# Sheet1.net
KiCad netlist of a schematic drawn in Altium Designer
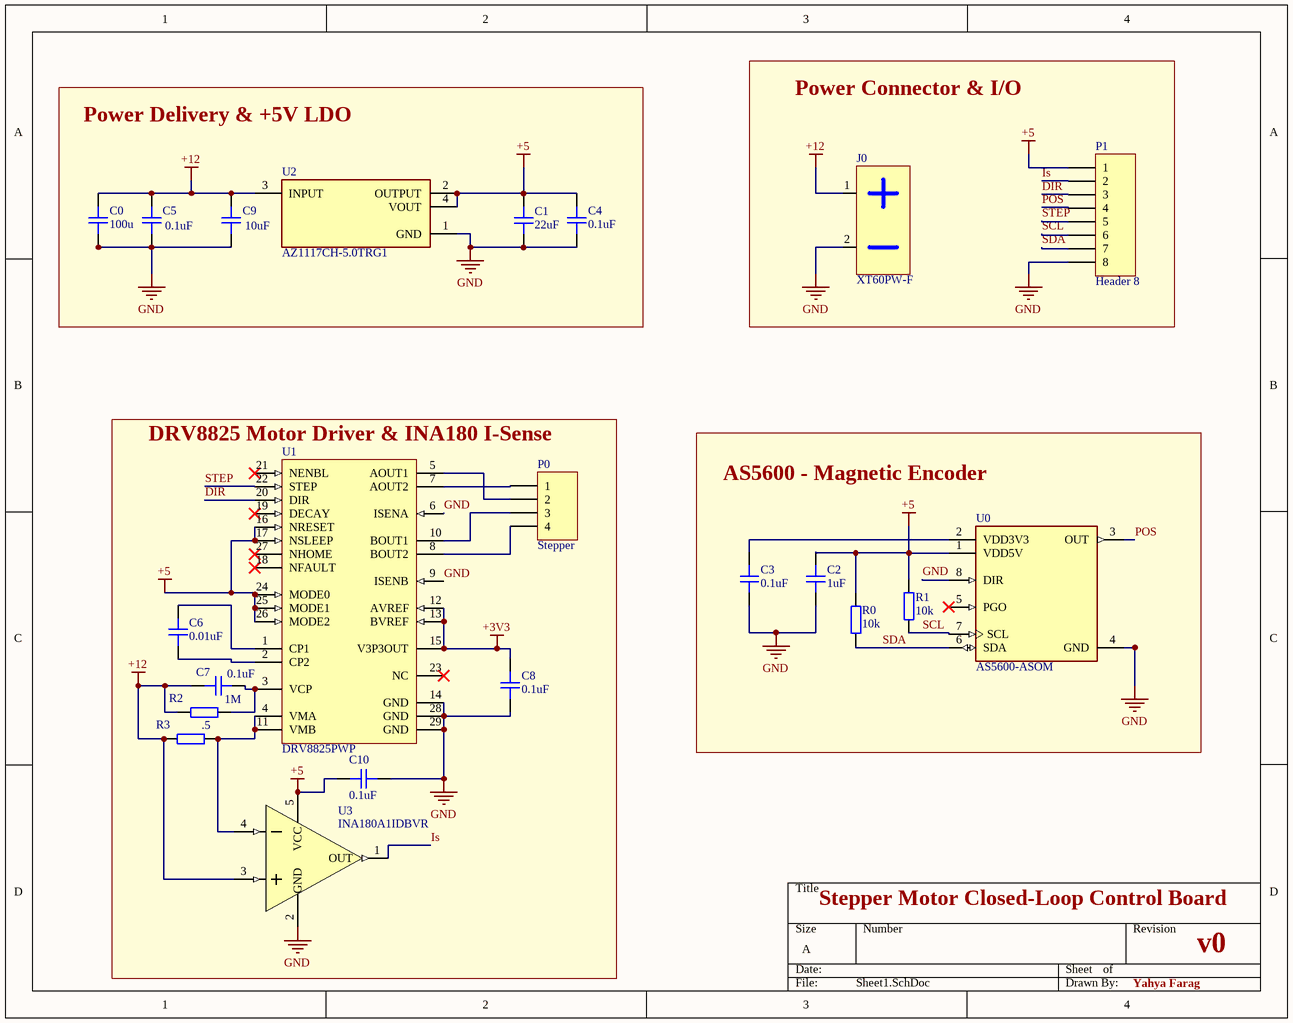
[diagram p0: Sheet1.SchDoc]

(export (version "E")
  (design (tool "Eeschema 10.0.6"))
  (components
    (comp (ref "C0")
      (value "100u")
      (footprint "CAP-EL-NP-5MM")
      (description "Capacitor SMD Electrolytic Non-Polarised 5mm Diameter - 12V")
      (fields (field (name "MANUFACTURER") "Nichicon"))
      (libsource (lib "Schematic-Lib-PhilsLab") (part "CAP_EL_NP_5MM"))
    )
    (comp (ref "C1")
      (value "22uF")
      (footprint "CAP_0805")
      (description "Capacitor SMD 0805 6V3")
      (libsource (lib "Schematic-Lib-PhilsLab") (part "CAP_0805_6V3"))
    )
    (comp (ref "C2")
      (value "1uF")
      (footprint "CAP_0805")
      (description "Capacitor SMD 0805 6V3")
      (libsource (lib "Schematic-Lib-PhilsLab") (part "CAP_0805_6V3"))
    )
    (comp (ref "C3")
      (value "0.1uF")
      (footprint "CAP_0805")
      (description "Capacitor SMD 0805 6V3")
      (libsource (lib "Schematic-Lib-PhilsLab") (part "CAP_0805_6V3"))
    )
    (comp (ref "C4")
      (value "0.1uF")
      (footprint "CAP_0805")
      (description "Capacitor SMD 0805 6V3")
      (libsource (lib "Schematic-Lib-PhilsLab") (part "CAP_0805_6V3"))
    )
    (comp (ref "C5")
      (value "0.1uF")
      (footprint "CAP_0805")
      (description "Capacitor SMD 0805 12V")
      (libsource (lib "Schematic-Lib-PhilsLab") (part "CAP_0805_6V3"))
    )
    (comp (ref "C6")
      (value "0.01uF")
      (footprint "CAP_0805")
      (description "Capacitor SMD 0805 50V")
      (libsource (lib "Schematic-Lib-PhilsLab") (part "CAP_0805_6V3"))
    )
    (comp (ref "C7")
      (value "0.1uF")
      (footprint "CAP_0805")
      (description "Capacitor SMD 0805 16V")
      (libsource (lib "Schematic-Lib-PhilsLab") (part "CAP_0805_6V3"))
    )
    (comp (ref "C8")
      (value "0.1uF")
      (footprint "CAP_0805")
      (description "Capacitor SMD 0805 6V3")
      (libsource (lib "Schematic-Lib-PhilsLab") (part "CAP_0805_6V3"))
    )
    (comp (ref "C9")
      (value "10uF")
      (footprint "CAP_0805")
      (description "Capacitor SMD 0805 12V")
      (libsource (lib "Schematic-Lib-PhilsLab") (part "CAP_0805_6V3"))
    )
    (comp (ref "C10")
      (value "0.1uF")
      (footprint "CAP_0805")
      (description "Capacitor SMD 0805 6V3")
      (libsource (lib "Schematic-Lib-PhilsLab") (part "CAP_0805_6V3"))
    )
    (comp (ref "J0")
      (value "XT60PW-F")
      (footprint "XT60PW-F")
      (description "XT60 horizontal female 2-pin AMASS")
      (fields (field (name "MANUFACTURER") "AMASS"))
      (libsource (lib "Schematic-Lib-PhilsLab") (part "XT60PW-F"))
    )
    (comp (ref "P0")
      (value "Stepper")
      (footprint "HDR1X4")
      (description "Header, 4-Pin")
      (fields (field (name "PUBLISHER") "Altium Limited"))
      (libsource (lib "Miscellaneous Connectors") (part "Header 4"))
    )
    (comp (ref "P1")
      (value "Header 8")
      (footprint "HDR1X8")
      (description "Header, 8-Pin")
      (fields (field (name "PUBLISHER") "Altium Limited"))
      (libsource (lib "Miscellaneous Connectors") (part "Header 8"))
    )
    (comp (ref "R0")
      (value "10k")
      (footprint "RES_0805")
      (description "Resistor SMD 0805")
      (libsource (lib "Schematic-Lib-PhilsLab") (part "RES_0805"))
    )
    (comp (ref "R1")
      (value "10k")
      (footprint "RES_0805")
      (description "Resistor SMD 0805")
      (libsource (lib "Schematic-Lib-PhilsLab") (part "RES_0805"))
    )
    (comp (ref "R2")
      (value "1M")
      (footprint "RES_0805")
      (description "Resistor SMD 0805")
      (libsource (lib "Schematic-Lib-PhilsLab") (part "RES_0805"))
    )
    (comp (ref "R3")
      (value ".5")
      (footprint "RES_0805")
      (description "Resistor SMD 0805")
      (libsource (lib "Schematic-Lib-PhilsLab") (part "RES_0805"))
    )
    (comp (ref "U0")
      (value "AS5600-ASOM")
      (footprint "FP-AS5600-ASOM-IPC_C")
      (description "SENSOR ANGLE 360DEG SMD")
      (libsource (lib "Altium Content Vault") (part "7a1e9824f8ff8a913d90a1366781b5b"))
    )
    (comp (ref "U1")
      (value "DRV8825PWP")
      (footprint "PWP0028C_L")
      (fields (field (name "TOLERANCE") "20%"))
      (libsource (lib "Altium Content Vault") (part "TI-DRV882XPWP28-XXXXXXXXXTP"))
    )
    (comp (ref "U2")
      (value "AZ1117CH-5.0TRG1")
      (footprint "FP-SOT223-MFG")
      (description "IC REG LINEAR 3.3V 800MA SOT223")
      (libsource (lib "Altium Content Vault") (part "bae10108a039f7d2bfd31a2f0f6c252"))
    )
    (comp (ref "U3")
      (value "INA180A1IDBVR")
      (footprint "SOT-23-5")
      (libsource (lib "Schematic-Lib-PhilsLab") (part "INA180A1IDBVR"))
    )
  )
  (nets
    (net (code "1") (name "+3V3") (class "Default")
      (node (ref "C8") (pin "1") (pinfunction "1_1") (pintype "passive"))
      (node (ref "U1") (pin "12") (pinfunction "AVREF_12") (pintype "input"))
      (node (ref "U1") (pin "13") (pinfunction "BVREF_13") (pintype "input"))
      (node (ref "U1") (pin "15") (pinfunction "V3P3OUT_15") (pintype "power_in"))
    )
    (net (code "2") (name "+5") (class "Default")
      (node (ref "C1") (pin "1") (pinfunction "1_1") (pintype "passive"))
      (node (ref "C10") (pin "1") (pinfunction "1_1") (pintype "passive"))
      (node (ref "C2") (pin "1") (pinfunction "1_1") (pintype "passive"))
      (node (ref "C4") (pin "1") (pinfunction "1_1") (pintype "passive"))
      (node (ref "P1") (pin "1") (pinfunction "1_1") (pintype "passive"))
      (node (ref "R0") (pin "1") (pinfunction "1_1") (pintype "passive"))
      (node (ref "R1") (pin "1") (pinfunction "1_1") (pintype "passive"))
      (node (ref "U0") (pin "1") (pinfunction "VDD5V_1") (pintype "power_in"))
      (node (ref "U1") (pin "16") (pinfunction "NRESET_16") (pintype "input"))
      (node (ref "U1") (pin "17") (pinfunction "NSLEEP_17") (pintype "input"))
      (node (ref "U1") (pin "24") (pinfunction "MODE0_24") (pintype "input"))
      (node (ref "U1") (pin "25") (pinfunction "MODE1_25") (pintype "input"))
      (node (ref "U1") (pin "26") (pinfunction "MODE2_26") (pintype "input"))
      (node (ref "U2") (pin "2") (pinfunction "OUTPUT_2") (pintype "power_in"))
      (node (ref "U2") (pin "4") (pinfunction "VOUT_4") (pintype "power_in"))
      (node (ref "U3") (pin "5") (pinfunction "VCC_5") (pintype "power_in"))
    )
    (net (code "3") (name "+12") (class "Default")
      (node (ref "C0") (pin "1") (pinfunction "1_1") (pintype "passive"))
      (node (ref "C5") (pin "1") (pinfunction "1_1") (pintype "passive"))
      (node (ref "C7") (pin "2") (pinfunction "2_2") (pintype "passive"))
      (node (ref "C9") (pin "1") (pinfunction "1_1") (pintype "passive"))
      (node (ref "J0") (pin "1") (pinfunction "V+_1") (pintype "power_in"))
      (node (ref "R2") (pin "2") (pinfunction "2_2") (pintype "passive"))
      (node (ref "R3") (pin "2") (pinfunction "2_2") (pintype "passive"))
      (node (ref "U2") (pin "3") (pinfunction "INPUT_3") (pintype "power_in"))
      (node (ref "U3") (pin "3") (pintype "input"))
    )
    (net (code "4") (name "/DIR") (class "Default")
      (node (ref "P1") (pin "3") (pinfunction "3_3") (pintype "passive"))
      (node (ref "U1") (pin "20") (pinfunction "DIR_20") (pintype "input"))
    )
    (net (code "5") (name "/Is") (class "Default")
      (node (ref "P1") (pin "2") (pinfunction "2_2") (pintype "passive"))
      (node (ref "U3") (pin "1") (pinfunction "OUT_1") (pintype "output"))
    )
    (net (code "6") (name "/POS") (class "Default")
      (node (ref "P1") (pin "4") (pinfunction "4_4") (pintype "passive"))
      (node (ref "U0") (pin "3") (pinfunction "OUT_3") (pintype "output"))
    )
    (net (code "7") (name "/SCL") (class "Default")
      (node (ref "P1") (pin "6") (pinfunction "6_6") (pintype "passive"))
      (node (ref "R1") (pin "2") (pinfunction "2_2") (pintype "passive"))
      (node (ref "U0") (pin "7") (pinfunction "SCL_7") (pintype "input"))
    )
    (net (code "8") (name "/SDA") (class "Default")
      (node (ref "P1") (pin "7") (pinfunction "7_7") (pintype "passive"))
      (node (ref "R0") (pin "2") (pinfunction "2_2") (pintype "passive"))
      (node (ref "U0") (pin "6") (pinfunction "SDA_6") (pintype "bidirectional"))
    )
    (net (code "9") (name "/STEP") (class "Default")
      (node (ref "P1") (pin "5") (pinfunction "5_5") (pintype "passive"))
      (node (ref "U1") (pin "22") (pinfunction "STEP_22") (pintype "input"))
    )
    (net (code "10") (name "GND") (class "Default")
      (node (ref "C0") (pin "2") (pinfunction "2_2") (pintype "passive"))
      (node (ref "C1") (pin "2") (pinfunction "2_2") (pintype "passive"))
      (node (ref "C10") (pin "2") (pinfunction "2_2") (pintype "passive"))
      (node (ref "C2") (pin "2") (pinfunction "2_2") (pintype "passive"))
      (node (ref "C3") (pin "2") (pinfunction "2_2") (pintype "passive"))
      (node (ref "C4") (pin "2") (pinfunction "2_2") (pintype "passive"))
      (node (ref "C5") (pin "2") (pinfunction "2_2") (pintype "passive"))
      (node (ref "C8") (pin "2") (pinfunction "2_2") (pintype "passive"))
      (node (ref "C9") (pin "2") (pinfunction "2_2") (pintype "passive"))
      (node (ref "J0") (pin "2") (pinfunction "V-_2") (pintype "power_in"))
      (node (ref "P1") (pin "8") (pinfunction "8_8") (pintype "passive"))
      (node (ref "U0") (pin "4") (pinfunction "GND_4") (pintype "power_in"))
      (node (ref "U0") (pin "8") (pinfunction "DIR_8") (pintype "input"))
      (node (ref "U1") (pin "14") (pinfunction "GND_14") (pintype "power_in"))
      (node (ref "U1") (pin "28") (pinfunction "GND_28") (pintype "power_in"))
      (node (ref "U1") (pin "29") (pinfunction "GND_29") (pintype "power_in"))
      (node (ref "U1") (pin "6") (pinfunction "ISENA_6") (pintype "input"))
      (node (ref "U1") (pin "9") (pinfunction "ISENB_9") (pintype "input"))
      (node (ref "U2") (pin "1") (pinfunction "GND_1") (pintype "power_in"))
      (node (ref "U3") (pin "2") (pinfunction "GND_2") (pintype "power_in"))
    )
    (net (code "11") (name "Net-(U0-VDD3V3)") (class "Default")
      (node (ref "C3") (pin "1") (pinfunction "1_1") (pintype "passive"))
      (node (ref "U0") (pin "2") (pinfunction "VDD3V3_2") (pintype "power_in"))
    )
    (net (code "12") (name "Net-(U1-AOUT1)") (class "Default")
      (node (ref "P0") (pin "2") (pinfunction "2_2") (pintype "passive"))
      (node (ref "U1") (pin "5") (pinfunction "AOUT1_5") (pintype "tri_state"))
    )
    (net (code "13") (name "Net-(U1-AOUT2)") (class "Default")
      (node (ref "P0") (pin "1") (pinfunction "1_1") (pintype "passive"))
      (node (ref "U1") (pin "7") (pinfunction "AOUT2_7") (pintype "tri_state"))
    )
    (net (code "14") (name "Net-(U1-BOUT1)") (class "Default")
      (node (ref "P0") (pin "3") (pinfunction "3_3") (pintype "passive"))
      (node (ref "U1") (pin "10") (pinfunction "BOUT1_10") (pintype "tri_state"))
    )
    (net (code "15") (name "Net-(U1-BOUT2)") (class "Default")
      (node (ref "P0") (pin "4") (pinfunction "4_4") (pintype "passive"))
      (node (ref "U1") (pin "8") (pinfunction "BOUT2_8") (pintype "tri_state"))
    )
    (net (code "16") (name "Net-(U1-CP1)") (class "Default")
      (node (ref "C6") (pin "1") (pinfunction "1_1") (pintype "passive"))
      (node (ref "U1") (pin "1") (pinfunction "CP1_1") (pintype "passive"))
    )
    (net (code "17") (name "Net-(U1-CP2)") (class "Default")
      (node (ref "C6") (pin "2") (pinfunction "2_2") (pintype "passive"))
      (node (ref "U1") (pin "2") (pinfunction "CP2_2") (pintype "passive"))
    )
    (net (code "18") (name "Net-(U1-VCP)") (class "Default")
      (node (ref "C7") (pin "1") (pinfunction "1_1") (pintype "passive"))
      (node (ref "R2") (pin "1") (pinfunction "1_1") (pintype "passive"))
      (node (ref "U1") (pin "3") (pinfunction "VCP_3") (pintype "passive"))
    )
    (net (code "19") (name "Net-(U1-VMA)") (class "Default")
      (node (ref "R3") (pin "1") (pinfunction "1_1") (pintype "passive"))
      (node (ref "U1") (pin "11") (pinfunction "VMB_11") (pintype "power_in"))
      (node (ref "U1") (pin "4") (pinfunction "VMA_4") (pintype "power_in"))
      (node (ref "U3") (pin "4") (pintype "input"))
    )
    (net (code "20") (name "unconnected-(U0-PGO-Pad5)") (class "Default")
      (node (ref "U0") (pin "5") (pinfunction "PGO_5") (pintype "input+no_connect"))
    )
    (net (code "21") (name "unconnected-(U1-DECAY-Pad19)") (class "Default")
      (node (ref "U1") (pin "19") (pinfunction "DECAY_19") (pintype "input+no_connect"))
    )
    (net (code "22") (name "unconnected-(U1-NC-Pad23)") (class "Default")
      (node (ref "U1") (pin "23") (pinfunction "NC_23") (pintype "passive+no_connect"))
    )
    (net (code "23") (name "unconnected-(U1-NENBL-Pad21)") (class "Default")
      (node (ref "U1") (pin "21") (pinfunction "NENBL_21") (pintype "input+no_connect"))
    )
    (net (code "24") (name "unconnected-(U1-NFAULT-Pad18)") (class "Default")
      (node (ref "U1") (pin "18") (pinfunction "NFAULT_18") (pintype "open_collector+no_connect"))
    )
    (net (code "25") (name "unconnected-(U1-NHOME-Pad27)") (class "Default")
      (node (ref "U1") (pin "27") (pinfunction "NHOME_27") (pintype "open_collector+no_connect"))
    )
  )
)
